# inrof1_2.net
KiCad netlist of a schematic drawn in EAGLE
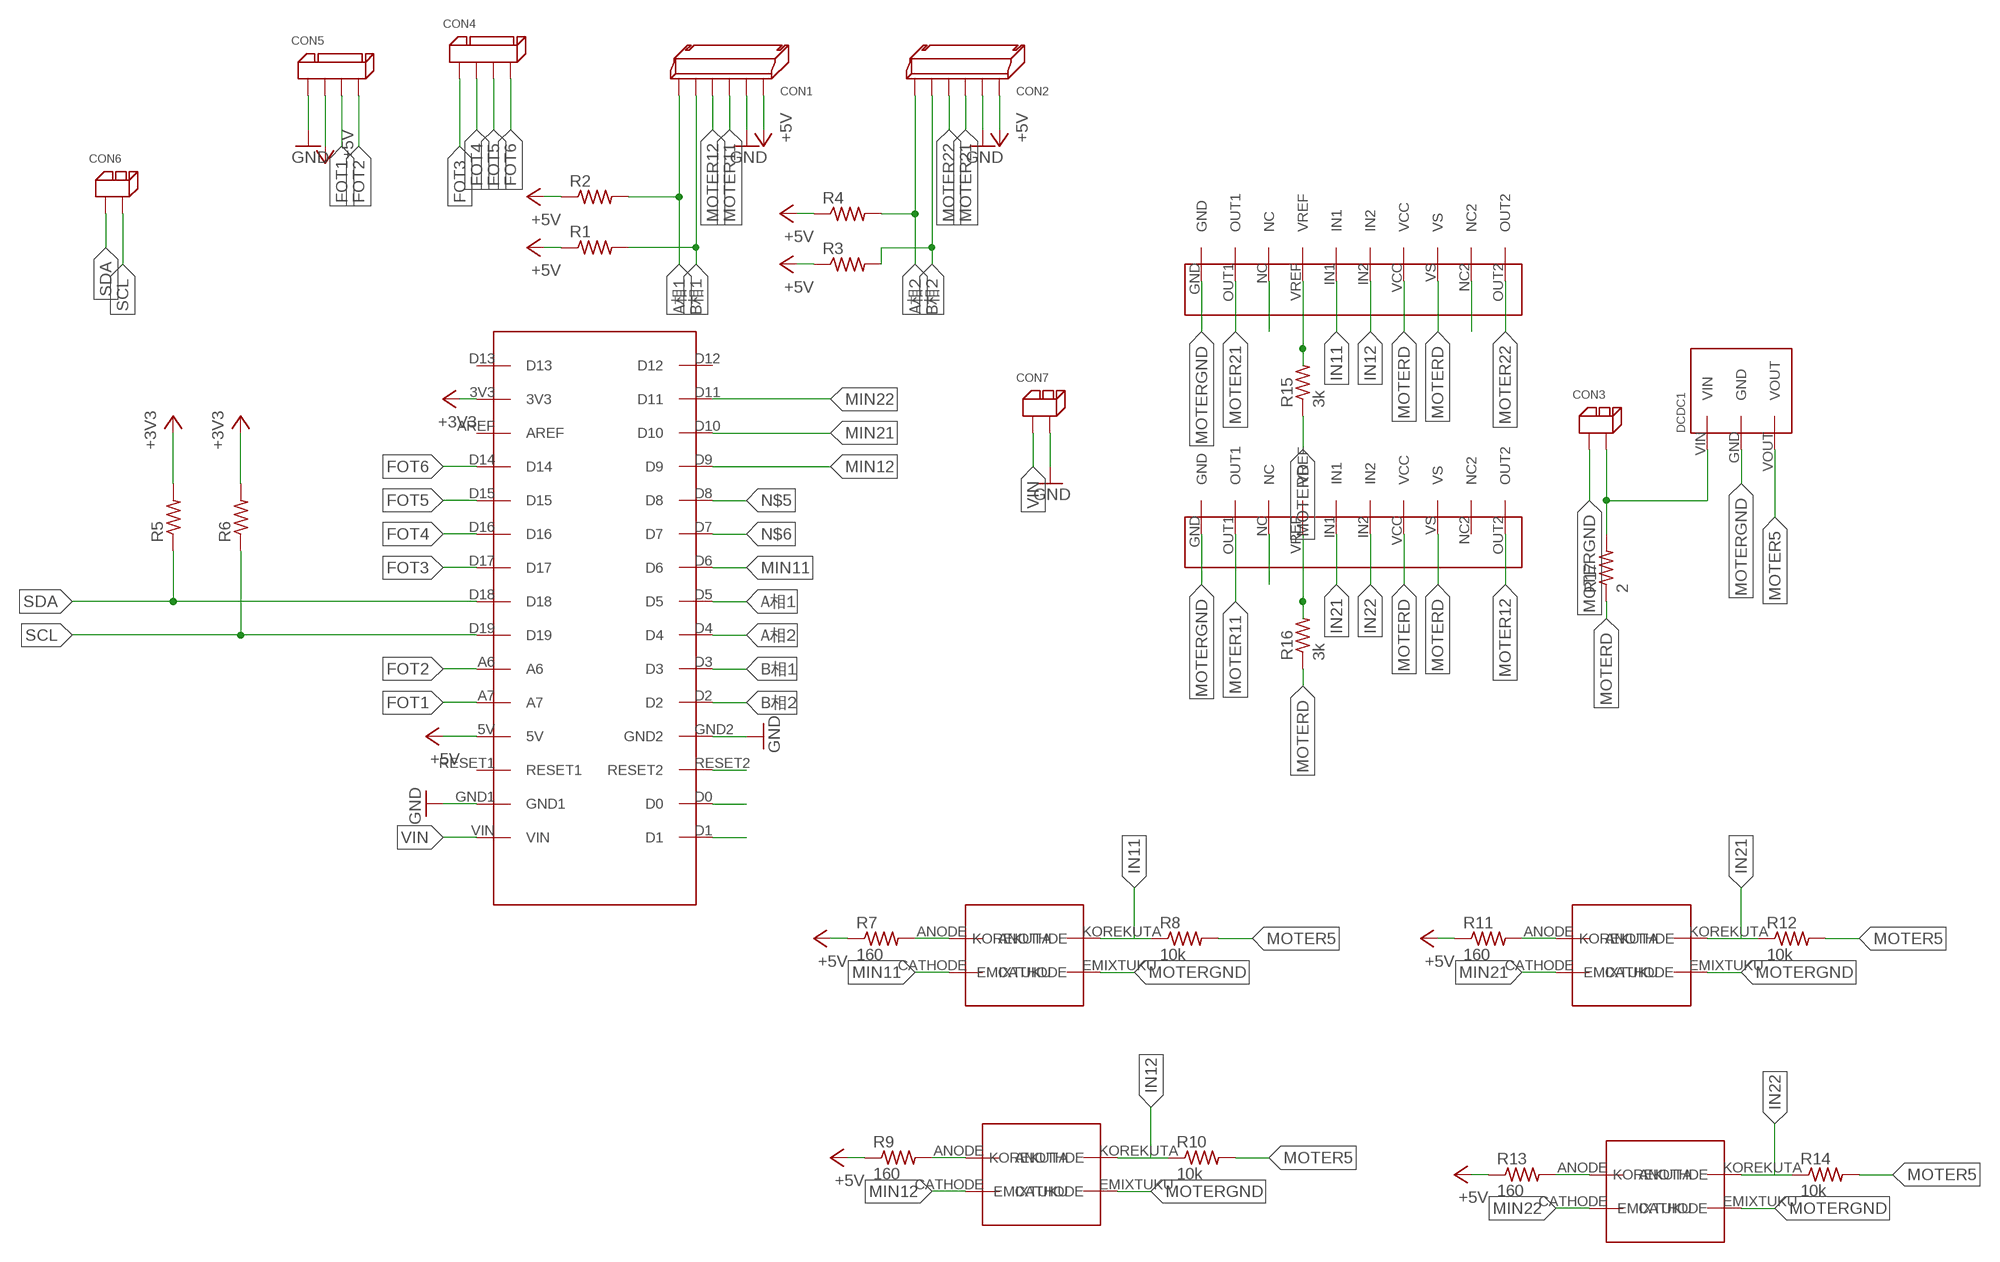
[diagram p0: schematic, sheet 1]

(export (version "E")
  (design (tool "Eeschema 10.0.6"))
  (components
    (comp (ref "CON1")
      (value "6PIN_SIDE")
      (footprint "eagle-import:6PIN_SIDE")
      (libsource (lib "eagle-import") (part "6PIN_SIDE"))
    )
    (comp (ref "CON2")
      (value "6PIN_SIDE")
      (footprint "eagle-import:6PIN_SIDE")
      (libsource (lib "eagle-import") (part "6PIN_SIDE"))
    )
    (comp (ref "CON3")
      (value "2PIN")
      (footprint "eagle-import:2PIN")
      (libsource (lib "eagle-import") (part "2PIN"))
    )
    (comp (ref "CON4")
      (value "4PIN")
      (footprint "eagle-import:4PIN")
      (libsource (lib "eagle-import") (part "4PIN"))
    )
    (comp (ref "CON5")
      (value "4PIN")
      (footprint "eagle-import:4PIN")
      (libsource (lib "eagle-import") (part "4PIN"))
    )
    (comp (ref "CON6")
      (value "2PIN")
      (footprint "eagle-import:2PIN")
      (libsource (lib "eagle-import") (part "2PIN"))
    )
    (comp (ref "CON7")
      (value "2PIN")
      (footprint "eagle-import:2PIN")
      (libsource (lib "eagle-import") (part "2PIN"))
    )
    (comp (ref "DCDC1")
      (value "5V1A_M78AR05-1")
      (footprint "eagle-import:5V1A_M78AR05-1")
      (libsource (lib "eagle-import") (part "5V1A_M78AR05-1"))
    )
    (comp (ref "R1")
      (value "R-US_0204/7")
      (footprint "eagle-import:0204_7")
      (libsource (lib "eagle-import") (part "R-US_0204/7"))
    )
    (comp (ref "R2")
      (value "R-US_0204/7")
      (footprint "eagle-import:0204_7")
      (libsource (lib "eagle-import") (part "R-US_0204/7"))
    )
    (comp (ref "R3")
      (value "R-US_0204/7")
      (footprint "eagle-import:0204_7")
      (libsource (lib "eagle-import") (part "R-US_0204/7"))
    )
    (comp (ref "R4")
      (value "R-US_0204/7")
      (footprint "eagle-import:0204_7")
      (libsource (lib "eagle-import") (part "R-US_0204/7"))
    )
    (comp (ref "R5")
      (value "R-US_0204/7")
      (footprint "eagle-import:0204_7")
      (libsource (lib "eagle-import") (part "R-US_0204/7"))
    )
    (comp (ref "R6")
      (value "R-US_0204/7")
      (footprint "eagle-import:0204_7")
      (libsource (lib "eagle-import") (part "R-US_0204/7"))
    )
    (comp (ref "R7")
      (value "160")
      (footprint "eagle-import:0204_7")
      (libsource (lib "eagle-import") (part "R-US_0204/7"))
    )
    (comp (ref "R8")
      (value "10k")
      (footprint "eagle-import:0204_7")
      (libsource (lib "eagle-import") (part "R-US_0204/7"))
    )
    (comp (ref "R9")
      (value "160")
      (footprint "eagle-import:0204_7")
      (libsource (lib "eagle-import") (part "R-US_0204/7"))
    )
    (comp (ref "R10")
      (value "10k")
      (footprint "eagle-import:0204_7")
      (libsource (lib "eagle-import") (part "R-US_0204/7"))
    )
    (comp (ref "R11")
      (value "160")
      (footprint "eagle-import:0204_7")
      (libsource (lib "eagle-import") (part "R-US_0204/7"))
    )
    (comp (ref "R12")
      (value "10k")
      (footprint "eagle-import:0204_7")
      (libsource (lib "eagle-import") (part "R-US_0204/7"))
    )
    (comp (ref "R13")
      (value "160")
      (footprint "eagle-import:0204_7")
      (libsource (lib "eagle-import") (part "R-US_0204/7"))
    )
    (comp (ref "R14")
      (value "10k")
      (footprint "eagle-import:0204_7")
      (libsource (lib "eagle-import") (part "R-US_0204/7"))
    )
    (comp (ref "R15")
      (value "3k")
      (footprint "eagle-import:0204_7")
      (libsource (lib "eagle-import") (part "R-US_0204/7"))
    )
    (comp (ref "R16")
      (value "3k")
      (footprint "eagle-import:0204_7")
      (libsource (lib "eagle-import") (part "R-US_0204/7"))
    )
    (comp (ref "R17")
      (value "2")
      (footprint "eagle-import:0204_7")
      (libsource (lib "eagle-import") (part "R-US_0204/7"))
    )
    (comp (ref "U$1")
      (value "ARDUINONANO")
      (footprint "eagle-import:ARDUINONANO")
      (libsource (lib "eagle-import") (part "ARDUINONANO"))
    )
    (comp (ref "U$2")
      (value "TA7291P")
      (footprint "eagle-import:TA7291P")
      (libsource (lib "eagle-import") (part "TA7291P"))
    )
    (comp (ref "U$3")
      (value "TA7291P")
      (footprint "eagle-import:TA7291P")
      (libsource (lib "eagle-import") (part "TA7291P"))
    )
    (comp (ref "U$4")
      (value "TLP561")
      (footprint "eagle-import:TLP561")
      (libsource (lib "eagle-import") (part "TLP561"))
    )
    (comp (ref "U$5")
      (value "TLP561")
      (footprint "eagle-import:TLP561")
      (libsource (lib "eagle-import") (part "TLP561"))
    )
    (comp (ref "U$6")
      (value "TLP561")
      (footprint "eagle-import:TLP561")
      (libsource (lib "eagle-import") (part "TLP561"))
    )
    (comp (ref "U$7")
      (value "TLP561")
      (footprint "eagle-import:TLP561")
      (libsource (lib "eagle-import") (part "TLP561"))
    )
  )
  (nets
    (net (code "1") (name "+3V3") (class "Default")
      (node (ref "R5") (pin "2") (pinfunction "2_2") (pintype "passive"))
      (node (ref "R6") (pin "2") (pinfunction "2_2") (pintype "passive"))
      (node (ref "U$1") (pin "3V3") (pinfunction "3V3_3V3") (pintype "bidirectional"))
    )
    (net (code "2") (name "+5V") (class "Default")
      (node (ref "CON1") (pin "P$6") (pinfunction "P$6_P$6") (pintype "bidirectional"))
      (node (ref "CON2") (pin "P$6") (pinfunction "P$6_P$6") (pintype "bidirectional"))
      (node (ref "CON5") (pin "P$2") (pinfunction "P$2_P$2") (pintype "bidirectional"))
      (node (ref "R1") (pin "1") (pinfunction "1_1") (pintype "passive"))
      (node (ref "R11") (pin "1") (pinfunction "1_1") (pintype "passive"))
      (node (ref "R13") (pin "1") (pinfunction "1_1") (pintype "passive"))
      (node (ref "R2") (pin "1") (pinfunction "1_1") (pintype "passive"))
      (node (ref "R3") (pin "1") (pinfunction "1_1") (pintype "passive"))
      (node (ref "R4") (pin "1") (pinfunction "1_1") (pintype "passive"))
      (node (ref "R7") (pin "1") (pinfunction "1_1") (pintype "passive"))
      (node (ref "R9") (pin "1") (pinfunction "1_1") (pintype "passive"))
      (node (ref "U$1") (pin "5V") (pinfunction "5V_5V") (pintype "bidirectional"))
    )
    (net (code "3") (name "A相1") (class "Default")
      (node (ref "CON1") (pin "P$1") (pinfunction "P$1_P$1") (pintype "bidirectional"))
      (node (ref "R2") (pin "2") (pinfunction "2_2") (pintype "passive"))
      (node (ref "U$1") (pin "D5") (pinfunction "D5_D5") (pintype "bidirectional"))
    )
    (net (code "4") (name "A相2") (class "Default")
      (node (ref "CON2") (pin "P$1") (pinfunction "P$1_P$1") (pintype "bidirectional"))
      (node (ref "R4") (pin "2") (pinfunction "2_2") (pintype "passive"))
      (node (ref "U$1") (pin "D4") (pinfunction "D4_D4") (pintype "bidirectional"))
    )
    (net (code "5") (name "B相1") (class "Default")
      (node (ref "CON1") (pin "P$2") (pinfunction "P$2_P$2") (pintype "bidirectional"))
      (node (ref "R1") (pin "2") (pinfunction "2_2") (pintype "passive"))
      (node (ref "U$1") (pin "D3") (pinfunction "D3_D3") (pintype "bidirectional"))
    )
    (net (code "6") (name "B相2") (class "Default")
      (node (ref "CON2") (pin "P$2") (pinfunction "P$2_P$2") (pintype "bidirectional"))
      (node (ref "R3") (pin "2") (pinfunction "2_2") (pintype "passive"))
      (node (ref "U$1") (pin "D2") (pinfunction "D2_D2") (pintype "bidirectional"))
    )
    (net (code "7") (name "FOT1") (class "Default")
      (node (ref "CON5") (pin "P$3") (pinfunction "P$3_P$3") (pintype "bidirectional"))
      (node (ref "U$1") (pin "A7") (pinfunction "A7_A7") (pintype "bidirectional"))
    )
    (net (code "8") (name "FOT2") (class "Default")
      (node (ref "CON5") (pin "P$4") (pinfunction "P$4_P$4") (pintype "bidirectional"))
      (node (ref "U$1") (pin "A6") (pinfunction "A6_A6") (pintype "bidirectional"))
    )
    (net (code "9") (name "FOT3") (class "Default")
      (node (ref "CON4") (pin "P$1") (pinfunction "P$1_P$1") (pintype "bidirectional"))
      (node (ref "U$1") (pin "D17") (pinfunction "D17_D17") (pintype "bidirectional"))
    )
    (net (code "10") (name "FOT4") (class "Default")
      (node (ref "CON4") (pin "P$2") (pinfunction "P$2_P$2") (pintype "bidirectional"))
      (node (ref "U$1") (pin "D16") (pinfunction "D16_D16") (pintype "bidirectional"))
    )
    (net (code "11") (name "FOT5") (class "Default")
      (node (ref "CON4") (pin "P$3") (pinfunction "P$3_P$3") (pintype "bidirectional"))
      (node (ref "U$1") (pin "D15") (pinfunction "D15_D15") (pintype "bidirectional"))
    )
    (net (code "12") (name "FOT6") (class "Default")
      (node (ref "CON4") (pin "P$4") (pinfunction "P$4_P$4") (pintype "bidirectional"))
      (node (ref "U$1") (pin "D14") (pinfunction "D14_D14") (pintype "bidirectional"))
    )
    (net (code "13") (name "GND") (class "Default")
      (node (ref "CON1") (pin "P$5") (pinfunction "P$5_P$5") (pintype "bidirectional"))
      (node (ref "CON2") (pin "P$5") (pinfunction "P$5_P$5") (pintype "bidirectional"))
      (node (ref "CON5") (pin "P$1") (pinfunction "P$1_P$1") (pintype "bidirectional"))
      (node (ref "CON7") (pin "P$2") (pinfunction "P$2_P$2") (pintype "bidirectional"))
      (node (ref "U$1") (pin "GND1") (pinfunction "GND1_GND1") (pintype "bidirectional"))
      (node (ref "U$1") (pin "GND2") (pinfunction "GND2_GND2") (pintype "bidirectional"))
    )
    (net (code "14") (name "IN11") (class "Default")
      (node (ref "R8") (pin "1") (pinfunction "1_1") (pintype "passive"))
      (node (ref "U$2") (pin "IN1") (pinfunction "IN1_IN1") (pintype "bidirectional"))
      (node (ref "U$4") (pin "KOREKUTA") (pinfunction "KOREKUTA_KOREKUTA") (pintype "bidirectional"))
    )
    (net (code "15") (name "IN12") (class "Default")
      (node (ref "R10") (pin "1") (pinfunction "1_1") (pintype "passive"))
      (node (ref "U$2") (pin "IN2") (pinfunction "IN2_IN2") (pintype "bidirectional"))
      (node (ref "U$5") (pin "KOREKUTA") (pinfunction "KOREKUTA_KOREKUTA") (pintype "bidirectional"))
    )
    (net (code "16") (name "IN21") (class "Default")
      (node (ref "R12") (pin "1") (pinfunction "1_1") (pintype "passive"))
      (node (ref "U$3") (pin "IN1") (pinfunction "IN1_IN1") (pintype "bidirectional"))
      (node (ref "U$6") (pin "KOREKUTA") (pinfunction "KOREKUTA_KOREKUTA") (pintype "bidirectional"))
    )
    (net (code "17") (name "IN22") (class "Default")
      (node (ref "R14") (pin "1") (pinfunction "1_1") (pintype "passive"))
      (node (ref "U$3") (pin "IN2") (pinfunction "IN2_IN2") (pintype "bidirectional"))
      (node (ref "U$7") (pin "KOREKUTA") (pinfunction "KOREKUTA_KOREKUTA") (pintype "bidirectional"))
    )
    (net (code "18") (name "MIN11") (class "Default")
      (node (ref "U$1") (pin "D6") (pinfunction "D6_D6") (pintype "bidirectional"))
      (node (ref "U$4") (pin "CATHODE") (pinfunction "CATHODE_CATHODE") (pintype "bidirectional"))
    )
    (net (code "19") (name "MIN12") (class "Default")
      (node (ref "U$1") (pin "D9") (pinfunction "D9_D9") (pintype "bidirectional"))
      (node (ref "U$5") (pin "CATHODE") (pinfunction "CATHODE_CATHODE") (pintype "bidirectional"))
    )
    (net (code "20") (name "MIN21") (class "Default")
      (node (ref "U$1") (pin "D10") (pinfunction "D10_D10") (pintype "bidirectional"))
      (node (ref "U$6") (pin "CATHODE") (pinfunction "CATHODE_CATHODE") (pintype "bidirectional"))
    )
    (net (code "21") (name "MIN22") (class "Default")
      (node (ref "U$1") (pin "D11") (pinfunction "D11_D11") (pintype "bidirectional"))
      (node (ref "U$7") (pin "CATHODE") (pinfunction "CATHODE_CATHODE") (pintype "bidirectional"))
    )
    (net (code "22") (name "MOTER5") (class "Default")
      (node (ref "DCDC1") (pin "VOUT") (pinfunction "VOUT_VOUT") (pintype "bidirectional"))
      (node (ref "R10") (pin "2") (pinfunction "2_2") (pintype "passive"))
      (node (ref "R12") (pin "2") (pinfunction "2_2") (pintype "passive"))
      (node (ref "R14") (pin "2") (pinfunction "2_2") (pintype "passive"))
      (node (ref "R8") (pin "2") (pinfunction "2_2") (pintype "passive"))
    )
    (net (code "23") (name "MOTER11") (class "Default")
      (node (ref "CON1") (pin "P$4") (pinfunction "P$4_P$4") (pintype "bidirectional"))
      (node (ref "U$3") (pin "OUT1") (pinfunction "OUT1_OUT1") (pintype "bidirectional"))
    )
    (net (code "24") (name "MOTER12") (class "Default")
      (node (ref "CON1") (pin "P$3") (pinfunction "P$3_P$3") (pintype "bidirectional"))
      (node (ref "U$3") (pin "OUT2") (pinfunction "OUT2_OUT2") (pintype "bidirectional"))
    )
    (net (code "25") (name "MOTER21") (class "Default")
      (node (ref "CON2") (pin "P$4") (pinfunction "P$4_P$4") (pintype "bidirectional"))
      (node (ref "U$2") (pin "OUT1") (pinfunction "OUT1_OUT1") (pintype "bidirectional"))
    )
    (net (code "26") (name "MOTER22") (class "Default")
      (node (ref "CON2") (pin "P$3") (pinfunction "P$3_P$3") (pintype "bidirectional"))
      (node (ref "U$2") (pin "OUT2") (pinfunction "OUT2_OUT2") (pintype "bidirectional"))
    )
    (net (code "27") (name "MOTERD") (class "Default")
      (node (ref "CON3") (pin "P$2") (pinfunction "P$2_P$2") (pintype "bidirectional"))
      (node (ref "DCDC1") (pin "VIN") (pinfunction "VIN_VIN") (pintype "bidirectional"))
      (node (ref "R15") (pin "1") (pinfunction "1_1") (pintype "passive"))
      (node (ref "R16") (pin "1") (pinfunction "1_1") (pintype "passive"))
      (node (ref "R17") (pin "1") (pinfunction "1_1") (pintype "passive"))
      (node (ref "R17") (pin "2") (pinfunction "2_2") (pintype "passive"))
      (node (ref "U$2") (pin "VCC") (pinfunction "VCC_VCC") (pintype "bidirectional"))
      (node (ref "U$2") (pin "VS") (pinfunction "VS_VS") (pintype "bidirectional"))
      (node (ref "U$3") (pin "VCC") (pinfunction "VCC_VCC") (pintype "bidirectional"))
      (node (ref "U$3") (pin "VS") (pinfunction "VS_VS") (pintype "bidirectional"))
    )
    (net (code "28") (name "MOTERGND") (class "Default")
      (node (ref "CON3") (pin "P$1") (pinfunction "P$1_P$1") (pintype "bidirectional"))
      (node (ref "DCDC1") (pin "GND") (pinfunction "GND_GND") (pintype "bidirectional"))
      (node (ref "U$2") (pin "GND") (pinfunction "GND_GND") (pintype "bidirectional"))
      (node (ref "U$3") (pin "GND") (pinfunction "GND_GND") (pintype "bidirectional"))
      (node (ref "U$4") (pin "EMIXTUKU") (pinfunction "EMIXTUKU_EMIXTUKU") (pintype "bidirectional"))
      (node (ref "U$5") (pin "EMIXTUKU") (pinfunction "EMIXTUKU_EMIXTUKU") (pintype "bidirectional"))
      (node (ref "U$6") (pin "EMIXTUKU") (pinfunction "EMIXTUKU_EMIXTUKU") (pintype "bidirectional"))
      (node (ref "U$7") (pin "EMIXTUKU") (pinfunction "EMIXTUKU_EMIXTUKU") (pintype "bidirectional"))
    )
    (net (code "29") (name "N$5") (class "Default")
      (node (ref "U$1") (pin "D8") (pinfunction "D8_D8") (pintype "bidirectional"))
    )
    (net (code "30") (name "N$6") (class "Default")
      (node (ref "U$1") (pin "D7") (pinfunction "D7_D7") (pintype "bidirectional"))
    )
    (net (code "31") (name "Net-(R15-Pad2)") (class "Default")
      (node (ref "R15") (pin "2") (pinfunction "2_2") (pintype "passive"))
      (node (ref "U$2") (pin "VREF") (pinfunction "VREF_VREF") (pintype "bidirectional"))
    )
    (net (code "32") (name "Net-(R16-Pad2)") (class "Default")
      (node (ref "R16") (pin "2") (pinfunction "2_2") (pintype "passive"))
      (node (ref "U$3") (pin "VREF") (pinfunction "VREF_VREF") (pintype "bidirectional"))
    )
    (net (code "33") (name "Net-(U$4-ANOTHDE)") (class "Default")
      (node (ref "R7") (pin "2") (pinfunction "2_2") (pintype "passive"))
      (node (ref "U$4") (pin "ANODE") (pinfunction "ANOTHDE_ANODE") (pintype "bidirectional"))
    )
    (net (code "34") (name "Net-(U$5-ANOTHDE)") (class "Default")
      (node (ref "R9") (pin "2") (pinfunction "2_2") (pintype "passive"))
      (node (ref "U$5") (pin "ANODE") (pinfunction "ANOTHDE_ANODE") (pintype "bidirectional"))
    )
    (net (code "35") (name "Net-(U$6-ANOTHDE)") (class "Default")
      (node (ref "R11") (pin "2") (pinfunction "2_2") (pintype "passive"))
      (node (ref "U$6") (pin "ANODE") (pinfunction "ANOTHDE_ANODE") (pintype "bidirectional"))
    )
    (net (code "36") (name "Net-(U$7-ANOTHDE)") (class "Default")
      (node (ref "R13") (pin "2") (pinfunction "2_2") (pintype "passive"))
      (node (ref "U$7") (pin "ANODE") (pinfunction "ANOTHDE_ANODE") (pintype "bidirectional"))
    )
    (net (code "37") (name "SCL") (class "Default")
      (node (ref "CON6") (pin "P$2") (pinfunction "P$2_P$2") (pintype "bidirectional"))
      (node (ref "R6") (pin "1") (pinfunction "1_1") (pintype "passive"))
      (node (ref "U$1") (pin "D19") (pinfunction "D19_D19") (pintype "bidirectional"))
    )
    (net (code "38") (name "SDA") (class "Default")
      (node (ref "CON6") (pin "P$1") (pinfunction "P$1_P$1") (pintype "bidirectional"))
      (node (ref "R5") (pin "1") (pinfunction "1_1") (pintype "passive"))
      (node (ref "U$1") (pin "D18") (pinfunction "D18_D18") (pintype "bidirectional"))
    )
    (net (code "39") (name "VIN") (class "Default")
      (node (ref "CON7") (pin "P$1") (pinfunction "P$1_P$1") (pintype "bidirectional"))
      (node (ref "U$1") (pin "VIN") (pinfunction "VIN_VIN") (pintype "bidirectional"))
    )
    (net (code "40") (name "unconnected-(U$1-PadAREF)") (class "Default")
      (node (ref "U$1") (pin "AREF") (pinfunction "AREF_AREF") (pintype "bidirectional"))
    )
    (net (code "41") (name "unconnected-(U$1-PadD0)") (class "Default")
      (node (ref "U$1") (pin "D0") (pinfunction "D0_D0") (pintype "bidirectional"))
    )
    (net (code "42") (name "unconnected-(U$1-PadD1)") (class "Default")
      (node (ref "U$1") (pin "D1") (pinfunction "D1_D1") (pintype "bidirectional"))
    )
    (net (code "43") (name "unconnected-(U$1-PadD12)") (class "Default")
      (node (ref "U$1") (pin "D12") (pinfunction "D12_D12") (pintype "bidirectional"))
    )
    (net (code "44") (name "unconnected-(U$1-PadD13)") (class "Default")
      (node (ref "U$1") (pin "D13") (pinfunction "D13_D13") (pintype "bidirectional"))
    )
    (net (code "45") (name "unconnected-(U$1-PadRESET1)") (class "Default")
      (node (ref "U$1") (pin "RESET1") (pinfunction "RESET1_RESET1") (pintype "bidirectional"))
    )
    (net (code "46") (name "unconnected-(U$1-PadRESET2)") (class "Default")
      (node (ref "U$1") (pin "RESET2") (pinfunction "RESET2_RESET2") (pintype "bidirectional"))
    )
    (net (code "47") (name "unconnected-(U$2-PadNC)") (class "Default")
      (node (ref "U$2") (pin "NC") (pinfunction "NC_NC") (pintype "bidirectional"))
    )
    (net (code "48") (name "unconnected-(U$2-PadNC2)") (class "Default")
      (node (ref "U$2") (pin "NC2") (pinfunction "NC2_NC2") (pintype "bidirectional"))
    )
    (net (code "49") (name "unconnected-(U$3-PadNC)") (class "Default")
      (node (ref "U$3") (pin "NC") (pinfunction "NC_NC") (pintype "bidirectional"))
    )
    (net (code "50") (name "unconnected-(U$3-PadNC2)") (class "Default")
      (node (ref "U$3") (pin "NC2") (pinfunction "NC2_NC2") (pintype "bidirectional"))
    )
  )
)
